# RF_AMP.net
KiCad netlist of a schematic drawn in Altium Designer
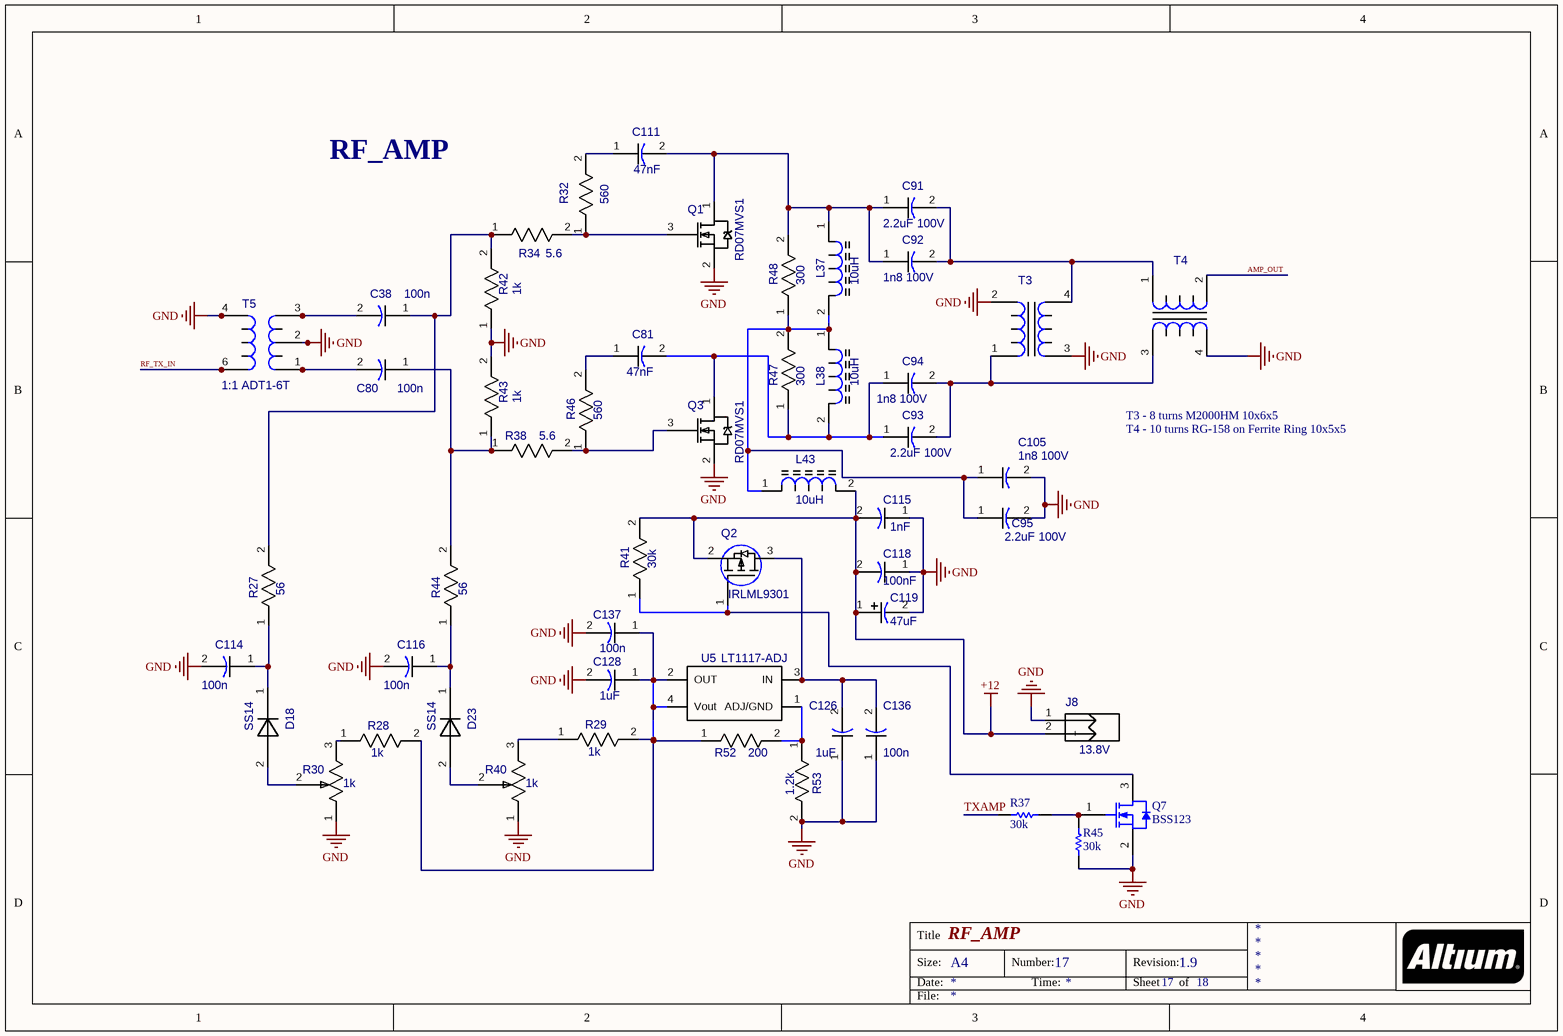
[diagram p0: RF_AMP.SchDoc]

(export (version "E")
  (design (tool "Eeschema 10.0.6"))
  (components
    (comp (ref "C38")
      (value "100n")
      (footprint "CAP_0805")
      (description "CAP_0805")
      (libsource (lib "*") (part "CAP_0805"))
    )
    (comp (ref "C80")
      (value "100n")
      (footprint "CAP_0805")
      (description "CAP_0805")
      (libsource (lib "*") (part "CAP_0805"))
    )
    (comp (ref "C81")
      (value "47nF")
      (footprint "CAP_1206")
      (description "CAP_1206")
      (libsource (lib "*") (part "CAP_1206"))
    )
    (comp (ref "C91")
      (value "2.2uF 100V")
      (footprint "CAP_1206")
      (description "CAP_1206")
      (libsource (lib "*") (part "CAP_1206"))
    )
    (comp (ref "C92")
      (value "1n8 100V")
      (footprint "CAP_1206")
      (description "CAP_1206")
      (libsource (lib "*") (part "CAP_1206"))
    )
    (comp (ref "C93")
      (value "2.2uF 100V")
      (footprint "CAP_1206")
      (description "CAP_1206")
      (libsource (lib "*") (part "CAP_1206"))
    )
    (comp (ref "C94")
      (value "1n8 100V")
      (footprint "CAP_1206")
      (description "CAP_1206")
      (libsource (lib "*") (part "CAP_1206"))
    )
    (comp (ref "C95")
      (value "2.2uF 100V")
      (footprint "CAP_1206")
      (description "CAP_1206")
      (libsource (lib "*") (part "CAP_1206"))
    )
    (comp (ref "C105")
      (value "1n8 100V")
      (footprint "CAP_1206")
      (description "CAP_1206")
      (libsource (lib "*") (part "CAP_1206"))
    )
    (comp (ref "C111")
      (value "47nF")
      (footprint "CAP_1206")
      (description "CAP_1206")
      (libsource (lib "*") (part "CAP_1206"))
    )
    (comp (ref "C114")
      (value "100n")
      (footprint "CAP_0805")
      (description "CAP_0805")
      (libsource (lib "*") (part "CAP_0805"))
    )
    (comp (ref "C115")
      (value "1nF")
      (footprint "CAP_0805")
      (description "CAP_0805")
      (libsource (lib "*") (part "CAP_0805"))
    )
    (comp (ref "C116")
      (value "100n")
      (footprint "CAP_0805")
      (description "CAP_0805")
      (libsource (lib "*") (part "CAP_0805"))
    )
    (comp (ref "C118")
      (value "100nF")
      (footprint "CAP_0805")
      (description "CAP_0805")
      (libsource (lib "*") (part "CAP_0805"))
    )
    (comp (ref "C119")
      (value "47uF")
      (footprint "CAPAE_6.6x6.6h5.4")
      (description "CAPAE_6.6x6.6h5.4")
      (libsource (lib "*") (part "CAPAE_6.6x6.6h5.4"))
    )
    (comp (ref "C126")
      (value "1uF")
      (footprint "CAP_0805")
      (description "CAP_0805")
      (libsource (lib "*") (part "CAP_0805"))
    )
    (comp (ref "C128")
      (value "1uF")
      (footprint "CAP_0805")
      (description "CAP_0805")
      (libsource (lib "*") (part "CAP_0805"))
    )
    (comp (ref "C136")
      (value "100n")
      (footprint "CAP_0805")
      (description "CAP_0805")
      (libsource (lib "*") (part "CAP_0805"))
    )
    (comp (ref "C137")
      (value "100n")
      (footprint "CAP_0805")
      (description "CAP_0805")
      (libsource (lib "*") (part "CAP_0805"))
    )
    (comp (ref "D18") (value "SS14") (footprint "SS14") (libsource (lib "*") (part "SS14")))
    (comp (ref "D23") (value "SS14") (footprint "SS14") (libsource (lib "*") (part "SS14")))
    (comp (ref "J8")
      (value "13.8V")
      (footprint "1986717-2")
      (description "JX2")
      (libsource (lib "*") (part "1986717-2"))
    )
    (comp (ref "L37")
      (value "10uH")
      (footprint "IND_FERRITE_CORE")
      (description "Inductor")
      (libsource (lib "*") (part "IND_FERRITE_CORE"))
    )
    (comp (ref "L38")
      (value "10uH")
      (footprint "IND_FERRITE_CORE")
      (description "Inductor")
      (libsource (lib "*") (part "IND_FERRITE_CORE"))
    )
    (comp (ref "L43")
      (value "10uH")
      (footprint "IND_FERRITE_CORE")
      (description "Inductor")
      (libsource (lib "*") (part "IND_FERRITE_CORE"))
    )
    (comp (ref "Q1") (value "RD07MVS1") (footprint "RD07MVS1") (libsource (lib "*") (part "RD07MVS1")))
    (comp (ref "Q2")
      (value "IRLML9301")
      (footprint "SOT23")
      (description "MOSFET")
      (libsource (lib "*") (part "MOSFET_ENH_PD"))
    )
    (comp (ref "Q3") (value "RD07MVS1") (footprint "RD07MVS1") (libsource (lib "*") (part "RD07MVS1")))
    (comp (ref "Q7")
      (value "BSS123")
      (footprint "FAIR-SOT23-3_V")
      (fields (field (name "MANUFACTURER") "Fairchild"))
      (libsource (lib "Altium Content Vault") (part "NEMOS-GSD-3"))
    )
    (comp (ref "R27")
      (value "56")
      (footprint "RES_0805")
      (description "RES_0805")
      (libsource (lib "*") (part "RES_0805"))
    )
    (comp (ref "R28")
      (value "1k")
      (footprint "RES_0805")
      (description "RES_0805")
      (libsource (lib "*") (part "RES_0805"))
    )
    (comp (ref "R29")
      (value "1k")
      (footprint "RES_0805")
      (description "RES_0805")
      (libsource (lib "*") (part "RES_0805"))
    )
    (comp (ref "R30")
      (value "1k")
      (footprint "306J")
      (description "306J")
      (fields (field (name "Comment") "ADJ-1k"))
      (libsource (lib "*") (part "306J"))
    )
    (comp (ref "R32")
      (value "560")
      (footprint "RES_0805")
      (description "RES_0805")
      (libsource (lib "*") (part "RES_0805"))
    )
    (comp (ref "R34")
      (value "5.6")
      (footprint "RES_1206")
      (description "RES_1206")
      (libsource (lib "*") (part "RES_1206"))
    )
    (comp (ref "R37")
      (value "30k")
      (footprint "RESC2013X60X40NL20T25")
      (description "RES_0805")
      (fields (field (name "MANUFACTURER") "Panasonic") (field (name "PART NUMBER") "ERA-6AEB303V"))
      (libsource (lib "Altium Content Vault") (part "RES"))
    )
    (comp (ref "R38")
      (value "5.6")
      (footprint "RES_1206")
      (description "RES_1206")
      (libsource (lib "*") (part "RES_1206"))
    )
    (comp (ref "R40")
      (value "1k")
      (footprint "306J")
      (description "306J")
      (fields (field (name "Comment") "ADJ-1k"))
      (libsource (lib "*") (part "306J"))
    )
    (comp (ref "R41")
      (value "30k")
      (footprint "RES_0805")
      (description "RES_0805")
      (libsource (lib "*") (part "RES_0805"))
    )
    (comp (ref "R42")
      (value "1k")
      (footprint "RES_0805")
      (description "RES_0805")
      (libsource (lib "*") (part "RES_0805"))
    )
    (comp (ref "R43")
      (value "1k")
      (footprint "RES_0805")
      (description "RES_0805")
      (libsource (lib "*") (part "RES_0805"))
    )
    (comp (ref "R44")
      (value "56")
      (footprint "RES_0805")
      (description "RES_0805")
      (libsource (lib "*") (part "RES_0805"))
    )
    (comp (ref "R45")
      (value "30k")
      (footprint "RESC2013X60X40NL20T25")
      (description "RES_0805")
      (fields (field (name "MANUFACTURER") "Panasonic") (field (name "PART NUMBER") "ERA-6AEB303V"))
      (libsource (lib "Altium Content Vault") (part "RES"))
    )
    (comp (ref "R46")
      (value "560")
      (footprint "RES_0805")
      (description "RES_0805")
      (libsource (lib "*") (part "RES_0805"))
    )
    (comp (ref "R47")
      (value "300")
      (footprint "RES_1206")
      (description "RES_1206")
      (libsource (lib "*") (part "RES_1206"))
    )
    (comp (ref "R48")
      (value "300")
      (footprint "RES_1206")
      (description "RES_1206")
      (libsource (lib "*") (part "RES_1206"))
    )
    (comp (ref "R52")
      (value "200")
      (footprint "RES_0805")
      (description "RES_0805")
      (libsource (lib "*") (part "RES_0805"))
    )
    (comp (ref "R53")
      (value "1.2k")
      (footprint "RES_0805")
      (description "RES_0805")
      (libsource (lib "*") (part "RES_0805"))
    )
    (comp (ref "T3")
      (value "8T M2000HM 10*6*5")
      (footprint "Rutrof")
      (description "Transformer")
      (libsource (lib "*") (part "TRANSF_ICORE"))
    )
    (comp (ref "T4")
      (value "10T on Fre Ring 10*5*5")
      (footprint "TRANSF_ICORE")
      (description "Transformer")
      (libsource (lib "*") (part "TRANSF_ICORE"))
    )
    (comp (ref "T5")
      (value "1:1 ADT1-6T")
      (footprint "TRANSF_ACORE2")
      (libsource (lib "RF-UNIT_1") (part "TRANSF_ACORE2"))
    )
    (comp (ref "U5")
      (value "LT1117-ADJ")
      (footprint "LT1117IST-ADJ")
      (description "LT1117IST-ADJ")
      (libsource (lib "*") (part "LT1117IST-ADJ"))
    )
  )
  (nets
    (net (code "1") (name "+12") (class "Default")
      (node (ref "C115") (pin "2") (pinfunction "2_2") (pintype "passive"))
      (node (ref "C118") (pin "2") (pinfunction "2_2") (pintype "passive"))
      (node (ref "C119") (pin "1") (pinfunction "PLUS_1") (pintype "passive"))
      (node (ref "J8") (pin "2") (pinfunction "+_2") (pintype "passive"))
      (node (ref "L43") (pin "2") (pinfunction "B_2") (pintype "passive"))
      (node (ref "Q2") (pin "2") (pinfunction "S_2") (pintype "passive"))
      (node (ref "R41") (pin "2") (pinfunction "2_2") (pintype "passive"))
    )
    (net (code "2") (name "/AMP_OUT") (class "Default")
      (node (ref "T4") (pin "2") (pinfunction "P2_2") (pintype "passive"))
    )
    (net (code "3") (name "/RF_TX_IN") (class "Default")
      (node (ref "T5") (pin "10") (pinfunction "0_10") (pintype "passive"))
      (node (ref "T5") (pin "6") (pinfunction "P1_6") (pintype "passive"))
    )
    (net (code "4") (name "/TXAMP") (class "Default")
      (node (ref "R37") (pin "2") (pinfunction "2_2") (pintype "passive"))
    )
    (net (code "5") (name "GND") (class "Default")
      (node (ref "C105") (pin "2") (pinfunction "2_2") (pintype "passive"))
      (node (ref "C114") (pin "2") (pinfunction "2_2") (pintype "passive"))
      (node (ref "C115") (pin "1") (pinfunction "1_1") (pintype "passive"))
      (node (ref "C116") (pin "2") (pinfunction "2_2") (pintype "passive"))
      (node (ref "C118") (pin "1") (pinfunction "1_1") (pintype "passive"))
      (node (ref "C119") (pin "2") (pinfunction "MINUS_2") (pintype "passive"))
      (node (ref "C126") (pin "1") (pinfunction "1_1") (pintype "passive"))
      (node (ref "C128") (pin "2") (pinfunction "2_2") (pintype "passive"))
      (node (ref "C136") (pin "1") (pinfunction "1_1") (pintype "passive"))
      (node (ref "C137") (pin "2") (pinfunction "2_2") (pintype "passive"))
      (node (ref "C95") (pin "2") (pinfunction "2_2") (pintype "passive"))
      (node (ref "J8") (pin "1") (pinfunction "-_1") (pintype "passive"))
      (node (ref "Q1") (pin "2") (pinfunction "S_2") (pintype "passive"))
      (node (ref "Q3") (pin "2") (pinfunction "S_2") (pintype "passive"))
      (node (ref "Q7") (pin "2") (pinfunction "S_2") (pintype "passive"))
      (node (ref "R30") (pin "1") (pinfunction "CCW_1") (pintype "passive"))
      (node (ref "R40") (pin "1") (pinfunction "CCW_1") (pintype "passive"))
      (node (ref "R42") (pin "1") (pinfunction "1_1") (pintype "passive"))
      (node (ref "R43") (pin "2") (pinfunction "2_2") (pintype "passive"))
      (node (ref "R45") (pin "1") (pinfunction "1_1") (pintype "passive"))
      (node (ref "R53") (pin "2") (pinfunction "2_2") (pintype "passive"))
      (node (ref "T3") (pin "2") (pinfunction "P2_2") (pintype "passive"))
      (node (ref "T3") (pin "3") (pinfunction "S1_3") (pintype "passive"))
      (node (ref "T4") (pin "4") (pinfunction "S2_4") (pintype "passive"))
      (node (ref "T5") (pin "11") (pinfunction "0_11") (pintype "passive"))
      (node (ref "T5") (pin "2") (pinfunction "S2_2") (pintype "passive"))
      (node (ref "T5") (pin "4") (pinfunction "P2_4") (pintype "passive"))
      (node (ref "T5") (pin "8") (pinfunction "S2_8") (pintype "passive"))
    )
    (net (code "6") (name "Net-(C38-Pad1)") (class "Default")
      (node (ref "C38") (pin "1") (pinfunction "1_1") (pintype "passive"))
      (node (ref "R27") (pin "2") (pinfunction "2_2") (pintype "passive"))
      (node (ref "R34") (pin "1") (pinfunction "1_1") (pintype "passive"))
      (node (ref "R42") (pin "2") (pinfunction "2_2") (pintype "passive"))
    )
    (net (code "7") (name "Net-(C80-Pad1)") (class "Default")
      (node (ref "C80") (pin "1") (pinfunction "1_1") (pintype "passive"))
      (node (ref "R38") (pin "1") (pinfunction "1_1") (pintype "passive"))
      (node (ref "R43") (pin "1") (pinfunction "1_1") (pintype "passive"))
      (node (ref "R44") (pin "2") (pinfunction "2_2") (pintype "passive"))
    )
    (net (code "8") (name "Net-(C81-Pad1)") (class "Default")
      (node (ref "C81") (pin "1") (pinfunction "1_1") (pintype "passive"))
      (node (ref "R46") (pin "2") (pinfunction "2_2") (pintype "passive"))
    )
    (net (code "9") (name "Net-(C111-Pad1)") (class "Default")
      (node (ref "C111") (pin "1") (pinfunction "1_1") (pintype "passive"))
      (node (ref "R32") (pin "2") (pinfunction "2_2") (pintype "passive"))
    )
    (net (code "10") (name "Net-(D18-A)") (class "Default")
      (node (ref "D18") (pin "2") (pinfunction "A_2") (pintype "passive"))
      (node (ref "R30") (pin "2") (pinfunction "W_2") (pintype "passive"))
    )
    (net (code "11") (name "Net-(D18-K)") (class "Default")
      (node (ref "C114") (pin "1") (pinfunction "1_1") (pintype "passive"))
      (node (ref "D18") (pin "1") (pinfunction "K_1") (pintype "passive"))
      (node (ref "R27") (pin "1") (pinfunction "1_1") (pintype "passive"))
    )
    (net (code "12") (name "Net-(D23-A)") (class "Default")
      (node (ref "D23") (pin "2") (pinfunction "A_2") (pintype "passive"))
      (node (ref "R40") (pin "2") (pinfunction "W_2") (pintype "passive"))
    )
    (net (code "13") (name "Net-(D23-K)") (class "Default")
      (node (ref "C116") (pin "1") (pinfunction "1_1") (pintype "passive"))
      (node (ref "D23") (pin "1") (pinfunction "K_1") (pintype "passive"))
      (node (ref "R44") (pin "1") (pinfunction "1_1") (pintype "passive"))
    )
    (net (code "14") (name "Net-(L37-A)") (class "Default")
      (node (ref "C111") (pin "2") (pinfunction "2_2") (pintype "passive"))
      (node (ref "C91") (pin "1") (pinfunction "1_1") (pintype "passive"))
      (node (ref "C92") (pin "1") (pinfunction "1_1") (pintype "passive"))
      (node (ref "L37") (pin "1") (pinfunction "A_1") (pintype "passive"))
      (node (ref "Q1") (pin "1") (pinfunction "D_1") (pintype "passive"))
      (node (ref "R48") (pin "2") (pinfunction "2_2") (pintype "passive"))
    )
    (net (code "15") (name "Net-(L37-B)") (class "Default")
      (node (ref "C105") (pin "1") (pinfunction "1_1") (pintype "passive"))
      (node (ref "C95") (pin "1") (pinfunction "1_1") (pintype "passive"))
      (node (ref "L37") (pin "2") (pinfunction "B_2") (pintype "passive"))
      (node (ref "L38") (pin "1") (pinfunction "A_1") (pintype "passive"))
      (node (ref "L43") (pin "1") (pinfunction "A_1") (pintype "passive"))
      (node (ref "R47") (pin "2") (pinfunction "2_2") (pintype "passive"))
      (node (ref "R48") (pin "1") (pinfunction "1_1") (pintype "passive"))
    )
    (net (code "16") (name "Net-(L38-B)") (class "Default")
      (node (ref "C81") (pin "2") (pinfunction "2_2") (pintype "passive"))
      (node (ref "C93") (pin "1") (pinfunction "1_1") (pintype "passive"))
      (node (ref "C94") (pin "1") (pinfunction "1_1") (pintype "passive"))
      (node (ref "L38") (pin "2") (pinfunction "B_2") (pintype "passive"))
      (node (ref "Q3") (pin "1") (pinfunction "D_1") (pintype "passive"))
      (node (ref "R47") (pin "1") (pinfunction "1_1") (pintype "passive"))
    )
    (net (code "17") (name "Net-(Q1-G)") (class "Default")
      (node (ref "Q1") (pin "3") (pinfunction "G_3") (pintype "passive"))
      (node (ref "R32") (pin "1") (pinfunction "1_1") (pintype "passive"))
      (node (ref "R34") (pin "2") (pinfunction "2_2") (pintype "passive"))
    )
    (net (code "18") (name "Net-(Q2-D)") (class "Default")
      (node (ref "C126") (pin "2") (pinfunction "2_2") (pintype "passive"))
      (node (ref "C136") (pin "2") (pinfunction "2_2") (pintype "passive"))
      (node (ref "Q2") (pin "3") (pinfunction "D_3") (pintype "passive"))
      (node (ref "U5") (pin "3") (pinfunction "IN_3") (pintype "passive"))
    )
    (net (code "19") (name "Net-(Q2-G)") (class "Default")
      (node (ref "Q2") (pin "1") (pinfunction "G_1") (pintype "passive"))
      (node (ref "Q7") (pin "3") (pinfunction "D_3") (pintype "passive"))
      (node (ref "R41") (pin "1") (pinfunction "1_1") (pintype "passive"))
    )
    (net (code "20") (name "Net-(Q3-G)") (class "Default")
      (node (ref "Q3") (pin "3") (pinfunction "G_3") (pintype "passive"))
      (node (ref "R38") (pin "2") (pinfunction "2_2") (pintype "passive"))
      (node (ref "R46") (pin "1") (pinfunction "1_1") (pintype "passive"))
    )
    (net (code "21") (name "Net-(Q7-G)") (class "Default")
      (node (ref "Q7") (pin "1") (pinfunction "G_1") (pintype "passive"))
      (node (ref "R37") (pin "1") (pinfunction "1_1") (pintype "passive"))
      (node (ref "R45") (pin "2") (pinfunction "2_2") (pintype "passive"))
    )
    (net (code "22") (name "Net-(R30-CW)") (class "Default")
      (node (ref "R28") (pin "1") (pinfunction "1_1") (pintype "passive"))
      (node (ref "R30") (pin "3") (pinfunction "CW_3") (pintype "passive"))
    )
    (net (code "23") (name "Net-(R40-CW)") (class "Default")
      (node (ref "R29") (pin "1") (pinfunction "1_1") (pintype "passive"))
      (node (ref "R40") (pin "3") (pinfunction "CW_3") (pintype "passive"))
    )
    (net (code "24") (name "Net-(T3-P1)") (class "Default")
      (node (ref "C93") (pin "2") (pinfunction "2_2") (pintype "passive"))
      (node (ref "C94") (pin "2") (pinfunction "2_2") (pintype "passive"))
      (node (ref "T3") (pin "1") (pinfunction "P1_1") (pintype "passive"))
      (node (ref "T4") (pin "3") (pinfunction "S1_3") (pintype "passive"))
    )
    (net (code "25") (name "Net-(T3-S2)") (class "Default")
      (node (ref "C91") (pin "2") (pinfunction "2_2") (pintype "passive"))
      (node (ref "C92") (pin "2") (pinfunction "2_2") (pintype "passive"))
      (node (ref "T3") (pin "4") (pinfunction "S2_4") (pintype "passive"))
      (node (ref "T4") (pin "1") (pinfunction "P1_1") (pintype "passive"))
    )
    (net (code "26") (name "Net-(T5-S1)") (class "Default")
      (node (ref "C80") (pin "2") (pinfunction "2_2") (pintype "passive"))
      (node (ref "T5") (pin "1") (pinfunction "S1_1") (pintype "passive"))
      (node (ref "T5") (pin "7") (pinfunction "0_7") (pintype "passive"))
    )
    (net (code "27") (name "Net-(T5-S3)") (class "Default")
      (node (ref "C38") (pin "2") (pinfunction "2_2") (pintype "passive"))
      (node (ref "T5") (pin "3") (pinfunction "S3_3") (pintype "passive"))
      (node (ref "T5") (pin "9") (pinfunction "0_9") (pintype "passive"))
    )
    (net (code "28") (name "Net-(U5-ADJ{slash}GND)") (class "Default")
      (node (ref "R52") (pin "2") (pinfunction "2_2") (pintype "passive"))
      (node (ref "R53") (pin "1") (pinfunction "1_1") (pintype "passive"))
      (node (ref "U5") (pin "1") (pinfunction "ADJ/GND_1") (pintype "passive"))
    )
    (net (code "29") (name "Net-(U5-OUT)") (class "Default")
      (node (ref "C128") (pin "1") (pinfunction "1_1") (pintype "passive"))
      (node (ref "C137") (pin "1") (pinfunction "1_1") (pintype "passive"))
      (node (ref "R28") (pin "2") (pinfunction "2_2") (pintype "passive"))
      (node (ref "R29") (pin "2") (pinfunction "2_2") (pintype "passive"))
      (node (ref "R52") (pin "1") (pinfunction "1_1") (pintype "passive"))
      (node (ref "U5") (pin "2") (pinfunction "OUT_2") (pintype "passive"))
      (node (ref "U5") (pin "4") (pinfunction "Vout_4") (pintype "passive"))
    )
  )
)
